# be_ca_thong_minh.net
KiCad netlist of a schematic drawn in Altium Designer
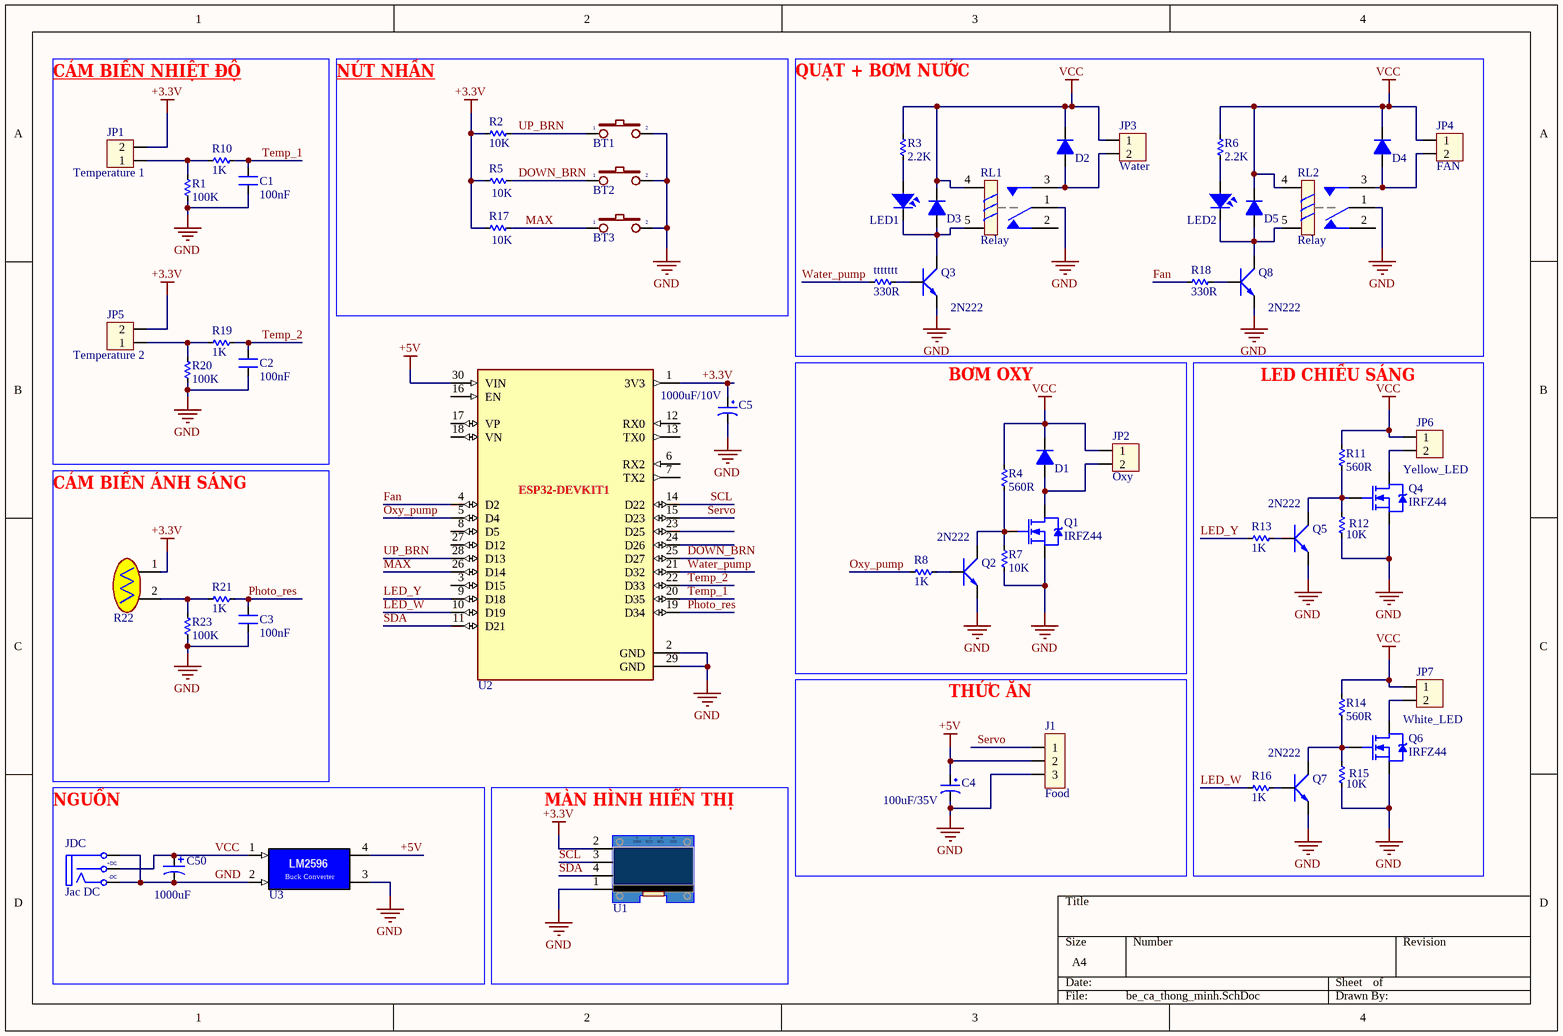
[diagram p0: be_ca_thong_minh.SchDoc]

(export (version "E")
  (design (tool "Eeschema 10.0.6"))
  (components
    (comp (ref "BT1") (value "BUTTON1") (footprint "SW4") (libsource (lib "Sang_Library") (part "BUTTON1")))
    (comp (ref "BT2") (value "BUTTON1") (footprint "SW4") (libsource (lib "Sang_Library") (part "BUTTON1")))
    (comp (ref "BT3") (value "BUTTON1") (footprint "SW4") (libsource (lib "Sang_Library") (part "BUTTON1")))
    (comp (ref "C1")
      (value "100nF")
      (footprint "CN2-O")
      (description "CAP-gom")
      (libsource (lib "Sang_Library") (part "CAP-gom"))
    )
    (comp (ref "C2")
      (value "100nF")
      (footprint "CN2-O")
      (description "CAP-gom")
      (libsource (lib "Sang_Library") (part "CAP-gom"))
    )
    (comp (ref "C3")
      (value "100nF")
      (footprint "CN2-O")
      (description "CAP-gom")
      (libsource (lib "Sang_Library") (part "CAP-gom"))
    )
    (comp (ref "C4")
      (value "100uF/35V")
      (footprint "CP1.5/3.4")
      (description "Cap 100uF/35V - 470uF/16V")
      (libsource (lib "Sang_Library") (part "CP3"))
    )
    (comp (ref "C5")
      (value "1000uF/10V")
      (footprint "CP1.5/3.4")
      (description "Cap 100uF/35V - 470uF/16V")
      (libsource (lib "Sang_Library") (part "CP3"))
    )
    (comp (ref "C50")
      (value "1000uF")
      (footprint "C8MM")
      (description "CAP-Radial")
      (fields (field (name "PUBLISHER") "Altium Limited"))
      (libsource (lib "Sang_Library") (part "CAP-Radial"))
    )
    (comp (ref "D1")
      (value "Diode  1N4007")
      (footprint "DO41-1A")
      (description "Diode 1A")
      (libsource (lib "Sang_Library") (part "Diode  1N4007"))
    )
    (comp (ref "D2")
      (value "Diode  1N4007")
      (footprint "DO41-1A")
      (description "Diode 1A")
      (libsource (lib "Sang_Library") (part "Diode  1N4007"))
    )
    (comp (ref "D3")
      (value "Diode  1N4007")
      (footprint "DO41-1A")
      (description "Diode 1A")
      (libsource (lib "Sang_Library") (part "Diode  1N4007"))
    )
    (comp (ref "D4")
      (value "Diode  1N4007")
      (footprint "DO41-1A")
      (description "Diode 1A")
      (libsource (lib "Sang_Library") (part "Diode  1N4007"))
    )
    (comp (ref "D5")
      (value "Diode  1N4007")
      (footprint "DO41-1A")
      (description "Diode 1A")
      (libsource (lib "Sang_Library") (part "Diode  1N4007"))
    )
    (comp (ref "J1") (value "Food") (footprint "JP3") (libsource (lib "Sang_Library") (part "JP3")))
    (comp (ref "JDC")
      (value "Jac DC")
      (footprint "DC-IN")
      (description "Jac DC input")
      (libsource (lib "Sang_Library") (part "DCIN"))
    )
    (comp (ref "JP1")
      (value "Temperature 1")
      (footprint "CON2")
      (description "Connector 2")
      (libsource (lib "") (part "Con2_1"))
    )
    (comp (ref "JP2")
      (value "Oxy")
      (footprint "CON2")
      (description "Connector 2")
      (libsource (lib "syhaunguyen") (part "Con2"))
    )
    (comp (ref "JP3")
      (value "Water")
      (footprint "CON2")
      (description "Connector 2")
      (libsource (lib "syhaunguyen") (part "Con2"))
    )
    (comp (ref "JP4")
      (value "FAN")
      (footprint "CON2")
      (description "Connector 2")
      (libsource (lib "syhaunguyen") (part "Con2"))
    )
    (comp (ref "JP5")
      (value "Temperature 2")
      (footprint "CON2")
      (description "Connector 2")
      (libsource (lib "") (part "Con2_1"))
    )
    (comp (ref "JP6")
      (value "Yellow_LED")
      (footprint "CON2")
      (description "Connector 2")
      (libsource (lib "syhaunguyen") (part "Con2"))
    )
    (comp (ref "JP7")
      (value "White_LED")
      (footprint "CON2")
      (description "Connector 2")
      (libsource (lib "syhaunguyen") (part "Con2"))
    )
    (comp (ref "LED1")
      (value "LED")
      (footprint "LED-5-BLUE")
      (description "LED Single colour Green and Red")
      (libsource (lib "Sang_Library") (part "LED"))
    )
    (comp (ref "LED2")
      (value "LED")
      (footprint "LED-5-BLUE")
      (description "LED Single colour Green and Red")
      (libsource (lib "Sang_Library") (part "LED"))
    )
    (comp (ref "Q1")
      (value "IRFZ44")
      (footprint "QTO-220H3")
      (description "HEXFET N-Channel Power MOSFET")
      (libsource (lib "Sang_Library") (part "IRFZ44"))
    )
    (comp (ref "Q2")
      (value "2N222")
      (footprint "TO92-123 - 1")
      (description "NPN 600mW, ECB")
      (libsource (lib "KhanhBK_Library_4") (part "2SC1815"))
    )
    (comp (ref "Q3")
      (value "2N222")
      (footprint "TO92-123 - 1")
      (description "NPN 600mW, ECB")
      (libsource (lib "KhanhBK_Library_4") (part "2SC1815"))
    )
    (comp (ref "Q4")
      (value "IRFZ44")
      (footprint "QTO-220H3")
      (description "HEXFET N-Channel Power MOSFET")
      (libsource (lib "Sang_Library") (part "IRFZ44"))
    )
    (comp (ref "Q5")
      (value "2N222")
      (footprint "TO92-123 - 1")
      (description "NPN 600mW, ECB")
      (libsource (lib "KhanhBK_Library_4") (part "2SC1815"))
    )
    (comp (ref "Q6")
      (value "IRFZ44")
      (footprint "QTO-220H3")
      (description "HEXFET N-Channel Power MOSFET")
      (libsource (lib "Sang_Library") (part "IRFZ44"))
    )
    (comp (ref "Q7")
      (value "2N222")
      (footprint "TO92-123 - 1")
      (description "NPN 600mW, ECB")
      (libsource (lib "KhanhBK_Library_4") (part "2SC1815"))
    )
    (comp (ref "Q8")
      (value "2N222")
      (footprint "TO92-123 - 1")
      (description "NPN 600mW, ECB")
      (libsource (lib "KhanhBK_Library_4") (part "2SC1815"))
    )
    (comp (ref "R1")
      (value "100K")
      (footprint "RES-1/4W")
      (description "Res")
      (fields
        (field (name "MANUFACTURER") "Generic Components")
        (field (name "PUBLISHER") "Altium Hobart Technology Centre")
      )
      (libsource (lib "Sang_Library") (part "Res_DIP"))
    )
    (comp (ref "R2")
      (value "10K")
      (footprint "RES-SMD-0805")
      (description "Resistor")
      (fields
        (field (name "MANUFACTURER") "Generic Components")
        (field (name "PUBLISHER") "Altium Hobart Technology Centre")
      )
      (libsource (lib "Sang_Library") (part "Res-SMD"))
    )
    (comp (ref "R3")
      (value "2.2K")
      (footprint "RES-1/4W")
      (description "Res")
      (fields
        (field (name "MANUFACTURER") "Generic Components")
        (field (name "PUBLISHER") "Altium Hobart Technology Centre")
      )
      (libsource (lib "Sang_Library") (part "Res_DIP"))
    )
    (comp (ref "R4")
      (value "560R")
      (footprint "RES-1/4W")
      (description "Res")
      (fields
        (field (name "MANUFACTURER") "Generic Components")
        (field (name "PUBLISHER") "Altium Hobart Technology Centre")
      )
      (libsource (lib "Sang_Library") (part "Res_DIP"))
    )
    (comp (ref "R5")
      (value "10K")
      (footprint "RES-SMD-0805")
      (description "Resistor")
      (fields
        (field (name "MANUFACTURER") "Generic Components")
        (field (name "PUBLISHER") "Altium Hobart Technology Centre")
      )
      (libsource (lib "Sang_Library") (part "Res-SMD"))
    )
    (comp (ref "R6")
      (value "2.2K")
      (footprint "RES-1/4W")
      (description "Res")
      (fields
        (field (name "MANUFACTURER") "Generic Components")
        (field (name "PUBLISHER") "Altium Hobart Technology Centre")
      )
      (libsource (lib "Sang_Library") (part "Res_DIP"))
    )
    (comp (ref "R7")
      (value "10K")
      (footprint "RES-1/4W")
      (description "Res")
      (fields
        (field (name "MANUFACTURER") "Generic Components")
        (field (name "PUBLISHER") "Altium Hobart Technology Centre")
      )
      (libsource (lib "Sang_Library") (part "Res_DIP"))
    )
    (comp (ref "R8")
      (value "1K")
      (footprint "RES-1/4W")
      (description "Res")
      (fields
        (field (name "MANUFACTURER") "Generic Components")
        (field (name "PUBLISHER") "Altium Hobart Technology Centre")
      )
      (libsource (lib "Sang_Library") (part "Res_DIP"))
    )
    (comp (ref "R10")
      (value "1K")
      (footprint "RES-1/4W")
      (description "Res")
      (fields
        (field (name "MANUFACTURER") "Generic Components")
        (field (name "PUBLISHER") "Altium Hobart Technology Centre")
      )
      (libsource (lib "Sang_Library") (part "Res_DIP"))
    )
    (comp (ref "R11")
      (value "560R")
      (footprint "RES-1/4W")
      (description "Res")
      (fields
        (field (name "MANUFACTURER") "Generic Components")
        (field (name "PUBLISHER") "Altium Hobart Technology Centre")
      )
      (libsource (lib "Sang_Library") (part "Res_DIP"))
    )
    (comp (ref "R12")
      (value "10K")
      (footprint "RES-1/4W")
      (description "Res")
      (fields
        (field (name "MANUFACTURER") "Generic Components")
        (field (name "PUBLISHER") "Altium Hobart Technology Centre")
      )
      (libsource (lib "Sang_Library") (part "Res_DIP"))
    )
    (comp (ref "R13")
      (value "1K")
      (footprint "RES-1/4W")
      (description "Res")
      (fields
        (field (name "MANUFACTURER") "Generic Components")
        (field (name "PUBLISHER") "Altium Hobart Technology Centre")
      )
      (libsource (lib "Sang_Library") (part "Res_DIP"))
    )
    (comp (ref "R14")
      (value "560R")
      (footprint "RES-1/4W")
      (description "Res")
      (fields
        (field (name "MANUFACTURER") "Generic Components")
        (field (name "PUBLISHER") "Altium Hobart Technology Centre")
      )
      (libsource (lib "Sang_Library") (part "Res_DIP"))
    )
    (comp (ref "R15")
      (value "10K")
      (footprint "RES-1/4W")
      (description "Res")
      (fields
        (field (name "MANUFACTURER") "Generic Components")
        (field (name "PUBLISHER") "Altium Hobart Technology Centre")
      )
      (libsource (lib "Sang_Library") (part "Res_DIP"))
    )
    (comp (ref "R16")
      (value "1K")
      (footprint "RES-1/4W")
      (description "Res")
      (fields
        (field (name "MANUFACTURER") "Generic Components")
        (field (name "PUBLISHER") "Altium Hobart Technology Centre")
      )
      (libsource (lib "Sang_Library") (part "Res_DIP"))
    )
    (comp (ref "R17")
      (value "10K")
      (footprint "RES-SMD-0805")
      (description "Resistor")
      (fields
        (field (name "MANUFACTURER") "Generic Components")
        (field (name "PUBLISHER") "Altium Hobart Technology Centre")
      )
      (libsource (lib "Sang_Library") (part "Res-SMD"))
    )
    (comp (ref "R18")
      (value "330R")
      (footprint "RES-1/4W")
      (description "Res")
      (fields
        (field (name "MANUFACTURER") "Generic Components")
        (field (name "PUBLISHER") "Altium Hobart Technology Centre")
      )
      (libsource (lib "Sang_Library") (part "Res_DIP"))
    )
    (comp (ref "R19")
      (value "1K")
      (footprint "RES-1/4W")
      (description "Res")
      (fields
        (field (name "MANUFACTURER") "Generic Components")
        (field (name "PUBLISHER") "Altium Hobart Technology Centre")
      )
      (libsource (lib "Sang_Library") (part "Res_DIP"))
    )
    (comp (ref "R20")
      (value "100K")
      (footprint "RES-1/4W")
      (description "Res")
      (fields
        (field (name "MANUFACTURER") "Generic Components")
        (field (name "PUBLISHER") "Altium Hobart Technology Centre")
      )
      (libsource (lib "Sang_Library") (part "Res_DIP"))
    )
    (comp (ref "R21")
      (value "1K")
      (footprint "RES-1/4W")
      (description "Res")
      (fields
        (field (name "MANUFACTURER") "Generic Components")
        (field (name "PUBLISHER") "Altium Hobart Technology Centre")
      )
      (libsource (lib "Sang_Library") (part "Res_DIP"))
    )
    (comp (ref "R22")
      (value "Photoresistor")
      (footprint "photoresistor")
      (libsource (lib "Huan") (part "Photoresistor"))
    )
    (comp (ref "R23")
      (value "100K")
      (footprint "RES-1/4W")
      (description "Res")
      (fields
        (field (name "MANUFACTURER") "Generic Components")
        (field (name "PUBLISHER") "Altium Hobart Technology Centre")
      )
      (libsource (lib "Sang_Library") (part "Res_DIP"))
    )
    (comp (ref "RL1")
      (value "Relay")
      (footprint "RL-05VDC-10A")
      (description "Relay SPDT 5 Pin")
      (libsource (lib "Sang_Library") (part "Relay 5VDC"))
    )
    (comp (ref "RL2")
      (value "Relay")
      (footprint "RL-05VDC-10A")
      (description "Relay SPDT 5 Pin")
      (libsource (lib "Sang_Library") (part "Relay 5VDC"))
    )
    (comp (ref "ttttttt")
      (value "330R")
      (footprint "RES-1/4W")
      (description "Res")
      (fields
        (field (name "MANUFACTURER") "Generic Components")
        (field (name "PUBLISHER") "Altium Hobart Technology Centre")
      )
      (libsource (lib "Sang_Library") (part "Res_DIP"))
    )
    (comp (ref "U1")
      (value "Oled_0.96")
      (footprint "OLED_0.96_MODULE")
      (libsource (lib "Huan") (part "Oled_0.96"))
    )
    (comp (ref "U2")
      (value "ESP32-DEVKIT_V1")
      (footprint "32_DEVKIT_V1")
      (libsource (lib "Huan") (part "ESP32-DEVKIT_V1"))
    )
    (comp (ref "U3")
      (value "LM2596_Module")
      (footprint "LM2596_Module")
      (libsource (lib "Huan") (part "LM2596_Module"))
    )
  )
  (nets
    (net (code "1") (name "+3.3V") (class "Default")
      (node (ref "C5") (pin "1") (pinfunction "1_1") (pintype "passive"))
      (node (ref "JP1") (pin "2") (pinfunction "2_2") (pintype "passive"))
      (node (ref "JP5") (pin "2") (pinfunction "2_2") (pintype "passive"))
      (node (ref "R17") (pin "2") (pinfunction "2_2") (pintype "passive"))
      (node (ref "R2") (pin "2") (pinfunction "2_2") (pintype "passive"))
      (node (ref "R22") (pin "1") (pinfunction "1_1") (pintype "passive"))
      (node (ref "R5") (pin "2") (pinfunction "2_2") (pintype "passive"))
      (node (ref "U1") (pin "2") (pinfunction "2_2") (pintype "passive"))
      (node (ref "U2") (pin "1") (pinfunction "3V3_1") (pintype "output"))
    )
    (net (code "2") (name "+5V") (class "Default")
      (node (ref "C4") (pin "1") (pinfunction "1_1") (pintype "passive"))
      (node (ref "J1") (pin "2") (pinfunction "2_2") (pintype "passive"))
      (node (ref "U2") (pin "30") (pinfunction "VIN_30") (pintype "input"))
      (node (ref "U3") (pin "4") (pinfunction "4_4") (pintype "power_in"))
    )
    (net (code "3") (name "/DOWN_BRN") (class "Default")
      (node (ref "BT2") (pin "1") (pinfunction "1_1") (pintype "passive"))
      (node (ref "R5") (pin "1") (pinfunction "1_1") (pintype "passive"))
      (node (ref "U2") (pin "25") (pinfunction "D27_25") (pintype "bidirectional"))
    )
    (net (code "4") (name "/Fan") (class "Default")
      (node (ref "R18") (pin "1") (pinfunction "1_1") (pintype "passive"))
      (node (ref "U2") (pin "4") (pinfunction "D2_4") (pintype "bidirectional"))
    )
    (net (code "5") (name "/LED_W") (class "Default")
      (node (ref "R16") (pin "1") (pinfunction "1_1") (pintype "passive"))
      (node (ref "U2") (pin "10") (pinfunction "D19_10") (pintype "bidirectional"))
    )
    (net (code "6") (name "/LED_Y") (class "Default")
      (node (ref "R13") (pin "1") (pinfunction "1_1") (pintype "passive"))
      (node (ref "U2") (pin "9") (pinfunction "D18_9") (pintype "bidirectional"))
    )
    (net (code "7") (name "/MAX") (class "Default")
      (node (ref "BT3") (pin "1") (pinfunction "1_1") (pintype "passive"))
      (node (ref "R17") (pin "1") (pinfunction "1_1") (pintype "passive"))
      (node (ref "U2") (pin "26") (pinfunction "D14_26") (pintype "bidirectional"))
    )
    (net (code "8") (name "/Oxy_pump") (class "Default")
      (node (ref "R8") (pin "1") (pinfunction "1_1") (pintype "passive"))
      (node (ref "U2") (pin "5") (pinfunction "D4_5") (pintype "bidirectional"))
    )
    (net (code "9") (name "/Photo_res") (class "Default")
      (node (ref "C3") (pin "2") (pinfunction "2_2") (pintype "passive"))
      (node (ref "R21") (pin "1") (pinfunction "1_1") (pintype "passive"))
      (node (ref "U2") (pin "19") (pinfunction "D34_19") (pintype "bidirectional"))
    )
    (net (code "10") (name "/SCL") (class "Default")
      (node (ref "U1") (pin "3") (pinfunction "3_3") (pintype "passive"))
      (node (ref "U2") (pin "14") (pinfunction "D22_14") (pintype "bidirectional"))
    )
    (net (code "11") (name "/SDA") (class "Default")
      (node (ref "U1") (pin "4") (pinfunction "4_4") (pintype "passive"))
      (node (ref "U2") (pin "11") (pinfunction "D21_11") (pintype "bidirectional"))
    )
    (net (code "12") (name "/Servo") (class "Default")
      (node (ref "J1") (pin "1") (pinfunction "1_1") (pintype "passive"))
      (node (ref "U2") (pin "15") (pinfunction "D23_15") (pintype "bidirectional"))
    )
    (net (code "13") (name "/Temp_1") (class "Default")
      (node (ref "C1") (pin "2") (pinfunction "2_2") (pintype "passive"))
      (node (ref "R10") (pin "1") (pinfunction "1_1") (pintype "passive"))
      (node (ref "U2") (pin "20") (pinfunction "D35_20") (pintype "bidirectional"))
    )
    (net (code "14") (name "/Temp_2") (class "Default")
      (node (ref "C2") (pin "2") (pinfunction "2_2") (pintype "passive"))
      (node (ref "R19") (pin "1") (pinfunction "1_1") (pintype "passive"))
      (node (ref "U2") (pin "22") (pinfunction "D33_22") (pintype "bidirectional"))
    )
    (net (code "15") (name "/UP_BRN") (class "Default")
      (node (ref "BT1") (pin "1") (pinfunction "1_1") (pintype "passive"))
      (node (ref "R2") (pin "1") (pinfunction "1_1") (pintype "passive"))
      (node (ref "U2") (pin "28") (pinfunction "D13_28") (pintype "bidirectional"))
    )
    (net (code "16") (name "/Water_pump") (class "Default")
      (node (ref "U2") (pin "21") (pinfunction "D32_21") (pintype "bidirectional"))
      (node (ref "ttttttt") (pin "1") (pinfunction "1_1") (pintype "passive"))
    )
    (net (code "17") (name "GND") (class "Default")
      (node (ref "BT1") (pin "2") (pinfunction "2_2") (pintype "passive"))
      (node (ref "BT2") (pin "2") (pinfunction "2_2") (pintype "passive"))
      (node (ref "BT3") (pin "2") (pinfunction "2_2") (pintype "passive"))
      (node (ref "C1") (pin "1") (pinfunction "1_1") (pintype "passive"))
      (node (ref "C2") (pin "1") (pinfunction "1_1") (pintype "passive"))
      (node (ref "C3") (pin "1") (pinfunction "1_1") (pintype "passive"))
      (node (ref "C4") (pin "2") (pinfunction "2_2") (pintype "passive"))
      (node (ref "C5") (pin "2") (pinfunction "2_2") (pintype "passive"))
      (node (ref "C50") (pin "2") (pinfunction "2_2") (pintype "passive"))
      (node (ref "J1") (pin "3") (pinfunction "3_3") (pintype "passive"))
      (node (ref "JDC") (pin "2") (pinfunction "TN_2") (pintype "passive"))
      (node (ref "JDC") (pin "3") (pinfunction "S_3") (pintype "power_in"))
      (node (ref "Q1") (pin "3") (pinfunction "S_3") (pintype "passive"))
      (node (ref "Q2") (pin "1") (pinfunction "E_1") (pintype "passive"))
      (node (ref "Q3") (pin "1") (pinfunction "E_1") (pintype "passive"))
      (node (ref "Q4") (pin "3") (pinfunction "S_3") (pintype "passive"))
      (node (ref "Q5") (pin "1") (pinfunction "E_1") (pintype "passive"))
      (node (ref "Q6") (pin "3") (pinfunction "S_3") (pintype "passive"))
      (node (ref "Q7") (pin "1") (pinfunction "E_1") (pintype "passive"))
      (node (ref "Q8") (pin "1") (pinfunction "E_1") (pintype "passive"))
      (node (ref "R1") (pin "1") (pinfunction "1_1") (pintype "passive"))
      (node (ref "R12") (pin "2") (pinfunction "2_2") (pintype "passive"))
      (node (ref "R15") (pin "2") (pinfunction "2_2") (pintype "passive"))
      (node (ref "R20") (pin "1") (pinfunction "1_1") (pintype "passive"))
      (node (ref "R23") (pin "1") (pinfunction "1_1") (pintype "passive"))
      (node (ref "R7") (pin "2") (pinfunction "2_2") (pintype "passive"))
      (node (ref "RL1") (pin "1") (pinfunction "1_1") (pintype "passive"))
      (node (ref "RL2") (pin "1") (pinfunction "1_1") (pintype "passive"))
      (node (ref "U1") (pin "1") (pinfunction "1_1") (pintype "passive"))
      (node (ref "U2") (pin "2") (pinfunction "GND_2") (pintype "power_in"))
      (node (ref "U2") (pin "29") (pinfunction "GND_29") (pintype "power_in"))
      (node (ref "U3") (pin "2") (pinfunction "2_2") (pintype "input"))
      (node (ref "U3") (pin "3") (pinfunction "3_3") (pintype "power_in"))
    )
    (net (code "18") (name "Net-(D2-Pad1)") (class "Default")
      (node (ref "D2") (pin "1") (pinfunction "1_1") (pintype "passive"))
      (node (ref "JP3") (pin "2") (pinfunction "2_2") (pintype "passive"))
      (node (ref "RL1") (pin "3") (pinfunction "3_3") (pintype "passive"))
    )
    (net (code "19") (name "Net-(D4-Pad1)") (class "Default")
      (node (ref "D4") (pin "1") (pinfunction "1_1") (pintype "passive"))
      (node (ref "JP4") (pin "2") (pinfunction "2_2") (pintype "passive"))
      (node (ref "RL2") (pin "3") (pinfunction "3_3") (pintype "passive"))
    )
    (net (code "20") (name "Net-(JP1-Pad1)") (class "Default")
      (node (ref "JP1") (pin "1") (pinfunction "1_1") (pintype "passive"))
      (node (ref "R1") (pin "2") (pinfunction "2_2") (pintype "passive"))
      (node (ref "R10") (pin "2") (pinfunction "2_2") (pintype "passive"))
    )
    (net (code "21") (name "Net-(JP5-Pad1)") (class "Default")
      (node (ref "JP5") (pin "1") (pinfunction "1_1") (pintype "passive"))
      (node (ref "R19") (pin "2") (pinfunction "2_2") (pintype "passive"))
      (node (ref "R20") (pin "2") (pinfunction "2_2") (pintype "passive"))
    )
    (net (code "22") (name "Net-(LED1-Pad1)") (class "Default")
      (node (ref "LED1") (pin "1") (pinfunction "1_1") (pintype "passive"))
      (node (ref "R3") (pin "1") (pinfunction "1_1") (pintype "passive"))
    )
    (net (code "23") (name "Net-(LED2-Pad1)") (class "Default")
      (node (ref "LED2") (pin "1") (pinfunction "1_1") (pintype "passive"))
      (node (ref "R6") (pin "1") (pinfunction "1_1") (pintype "passive"))
    )
    (net (code "24") (name "Net-(Q1-D)") (class "Default")
      (node (ref "D1") (pin "1") (pinfunction "1_1") (pintype "passive"))
      (node (ref "JP2") (pin "2") (pinfunction "2_2") (pintype "passive"))
      (node (ref "Q1") (pin "2") (pinfunction "D_2") (pintype "passive"))
    )
    (net (code "25") (name "Net-(Q1-G)") (class "Default")
      (node (ref "Q1") (pin "1") (pinfunction "G_1") (pintype "passive"))
      (node (ref "Q2") (pin "2") (pinfunction "C_2") (pintype "passive"))
      (node (ref "R4") (pin "2") (pinfunction "2_2") (pintype "passive"))
      (node (ref "R7") (pin "1") (pinfunction "1_1") (pintype "passive"))
    )
    (net (code "26") (name "Net-(Q2-B)") (class "Default")
      (node (ref "Q2") (pin "3") (pinfunction "B_3") (pintype "passive"))
      (node (ref "R8") (pin "2") (pinfunction "2_2") (pintype "passive"))
    )
    (net (code "27") (name "Net-(Q3-B)") (class "Default")
      (node (ref "Q3") (pin "3") (pinfunction "B_3") (pintype "passive"))
      (node (ref "ttttttt") (pin "2") (pinfunction "2_2") (pintype "passive"))
    )
    (net (code "28") (name "Net-(Q3-C)") (class "Default")
      (node (ref "D3") (pin "1") (pinfunction "1_1") (pintype "passive"))
      (node (ref "LED1") (pin "2") (pinfunction "2_2") (pintype "passive"))
      (node (ref "Q3") (pin "2") (pinfunction "C_2") (pintype "passive"))
      (node (ref "RL1") (pin "5") (pinfunction "5_5") (pintype "passive"))
    )
    (net (code "29") (name "Net-(Q4-D)") (class "Default")
      (node (ref "JP6") (pin "2") (pinfunction "2_2") (pintype "passive"))
      (node (ref "Q4") (pin "2") (pinfunction "D_2") (pintype "passive"))
    )
    (net (code "30") (name "Net-(Q4-G)") (class "Default")
      (node (ref "Q4") (pin "1") (pinfunction "G_1") (pintype "passive"))
      (node (ref "Q5") (pin "2") (pinfunction "C_2") (pintype "passive"))
      (node (ref "R11") (pin "2") (pinfunction "2_2") (pintype "passive"))
      (node (ref "R12") (pin "1") (pinfunction "1_1") (pintype "passive"))
    )
    (net (code "31") (name "Net-(Q5-B)") (class "Default")
      (node (ref "Q5") (pin "3") (pinfunction "B_3") (pintype "passive"))
      (node (ref "R13") (pin "2") (pinfunction "2_2") (pintype "passive"))
    )
    (net (code "32") (name "Net-(Q6-D)") (class "Default")
      (node (ref "JP7") (pin "2") (pinfunction "2_2") (pintype "passive"))
      (node (ref "Q6") (pin "2") (pinfunction "D_2") (pintype "passive"))
    )
    (net (code "33") (name "Net-(Q6-G)") (class "Default")
      (node (ref "Q6") (pin "1") (pinfunction "G_1") (pintype "passive"))
      (node (ref "Q7") (pin "2") (pinfunction "C_2") (pintype "passive"))
      (node (ref "R14") (pin "2") (pinfunction "2_2") (pintype "passive"))
      (node (ref "R15") (pin "1") (pinfunction "1_1") (pintype "passive"))
    )
    (net (code "34") (name "Net-(Q7-B)") (class "Default")
      (node (ref "Q7") (pin "3") (pinfunction "B_3") (pintype "passive"))
      (node (ref "R16") (pin "2") (pinfunction "2_2") (pintype "passive"))
    )
    (net (code "35") (name "Net-(Q8-B)") (class "Default")
      (node (ref "Q8") (pin "3") (pinfunction "B_3") (pintype "passive"))
      (node (ref "R18") (pin "2") (pinfunction "2_2") (pintype "passive"))
    )
    (net (code "36") (name "Net-(Q8-C)") (class "Default")
      (node (ref "D5") (pin "1") (pinfunction "1_1") (pintype "passive"))
      (node (ref "LED2") (pin "2") (pinfunction "2_2") (pintype "passive"))
      (node (ref "Q8") (pin "2") (pinfunction "C_2") (pintype "passive"))
      (node (ref "RL2") (pin "5") (pinfunction "5_5") (pintype "passive"))
    )
    (net (code "37") (name "Net-(R21-Pad2)") (class "Default")
      (node (ref "R21") (pin "2") (pinfunction "2_2") (pintype "passive"))
      (node (ref "R22") (pin "2") (pinfunction "2_2") (pintype "passive"))
      (node (ref "R23") (pin "2") (pinfunction "2_2") (pintype "passive"))
    )
    (net (code "38") (name "VCC") (class "Default")
      (node (ref "C50") (pin "1") (pinfunction "1_1") (pintype "passive"))
      (node (ref "D1") (pin "2") (pinfunction "2_2") (pintype "passive"))
      (node (ref "D2") (pin "2") (pinfunction "2_2") (pintype "passive"))
      (node (ref "D3") (pin "2") (pinfunction "2_2") (pintype "passive"))
      (node (ref "D4") (pin "2") (pinfunction "2_2") (pintype "passive"))
      (node (ref "D5") (pin "2") (pinfunction "2_2") (pintype "passive"))
      (node (ref "JDC") (pin "1") (pinfunction "T_1") (pintype "passive"))
      (node (ref "JP2") (pin "1") (pinfunction "1_1") (pintype "passive"))
      (node (ref "JP3") (pin "1") (pinfunction "1_1") (pintype "passive"))
      (node (ref "JP4") (pin "1") (pinfunction "1_1") (pintype "passive"))
      (node (ref "JP6") (pin "1") (pinfunction "1_1") (pintype "passive"))
      (node (ref "JP7") (pin "1") (pinfunction "1_1") (pintype "passive"))
      (node (ref "R11") (pin "1") (pinfunction "1_1") (pintype "passive"))
      (node (ref "R14") (pin "1") (pinfunction "1_1") (pintype "passive"))
      (node (ref "R3") (pin "2") (pinfunction "2_2") (pintype "passive"))
      (node (ref "R4") (pin "1") (pinfunction "1_1") (pintype "passive"))
      (node (ref "R6") (pin "2") (pinfunction "2_2") (pintype "passive"))
      (node (ref "RL1") (pin "4") (pinfunction "4_4") (pintype "passive"))
      (node (ref "RL2") (pin "4") (pinfunction "4_4") (pintype "passive"))
      (node (ref "U3") (pin "1") (pinfunction "1_1") (pintype "input"))
    )
    (net (code "39") (name "unconnected-(RL1-Pad2)") (class "Default")
      (node (ref "RL1") (pin "2") (pinfunction "2_2") (pintype "passive"))
    )
    (net (code "40") (name "unconnected-(RL2-Pad2)") (class "Default")
      (node (ref "RL2") (pin "2") (pinfunction "2_2") (pintype "passive"))
    )
    (net (code "41") (name "unconnected-(U2-D5-Pad8)") (class "Default")
      (node (ref "U2") (pin "8") (pinfunction "D5_8") (pintype "bidirectional"))
    )
    (net (code "42") (name "unconnected-(U2-D12-Pad27)") (class "Default")
      (node (ref "U2") (pin "27") (pinfunction "D12_27") (pintype "bidirectional"))
    )
    (net (code "43") (name "unconnected-(U2-D15-Pad3)") (class "Default")
      (node (ref "U2") (pin "3") (pinfunction "D15_3") (pintype "bidirectional"))
    )
    (net (code "44") (name "unconnected-(U2-D25-Pad23)") (class "Default")
      (node (ref "U2") (pin "23") (pinfunction "D25_23") (pintype "bidirectional"))
    )
    (net (code "45") (name "unconnected-(U2-D26-Pad24)") (class "Default")
      (node (ref "U2") (pin "24") (pinfunction "D26_24") (pintype "bidirectional"))
    )
    (net (code "46") (name "unconnected-(U2-EN-Pad16)") (class "Default")
      (node (ref "U2") (pin "16") (pinfunction "EN_16") (pintype "input"))
    )
    (net (code "47") (name "unconnected-(U2-RX0-Pad12)") (class "Default")
      (node (ref "U2") (pin "12") (pinfunction "RX0_12") (pintype "input"))
    )
    (net (code "48") (name "unconnected-(U2-RX2-Pad6)") (class "Default")
      (node (ref "U2") (pin "6") (pinfunction "RX2_6") (pintype "input"))
    )
    (net (code "49") (name "unconnected-(U2-TX0-Pad13)") (class "Default")
      (node (ref "U2") (pin "13") (pinfunction "TX0_13") (pintype "output"))
    )
    (net (code "50") (name "unconnected-(U2-TX2-Pad7)") (class "Default")
      (node (ref "U2") (pin "7") (pinfunction "TX2_7") (pintype "output"))
    )
    (net (code "51") (name "unconnected-(U2-VN-Pad18)") (class "Default")
      (node (ref "U2") (pin "18") (pinfunction "VN_18") (pintype "bidirectional"))
    )
    (net (code "52") (name "unconnected-(U2-VP-Pad17)") (class "Default")
      (node (ref "U2") (pin "17") (pinfunction "VP_17") (pintype "bidirectional"))
    )
  )
)
